# BrewMonitorEagle.net
KiCad netlist of a schematic drawn in EAGLE
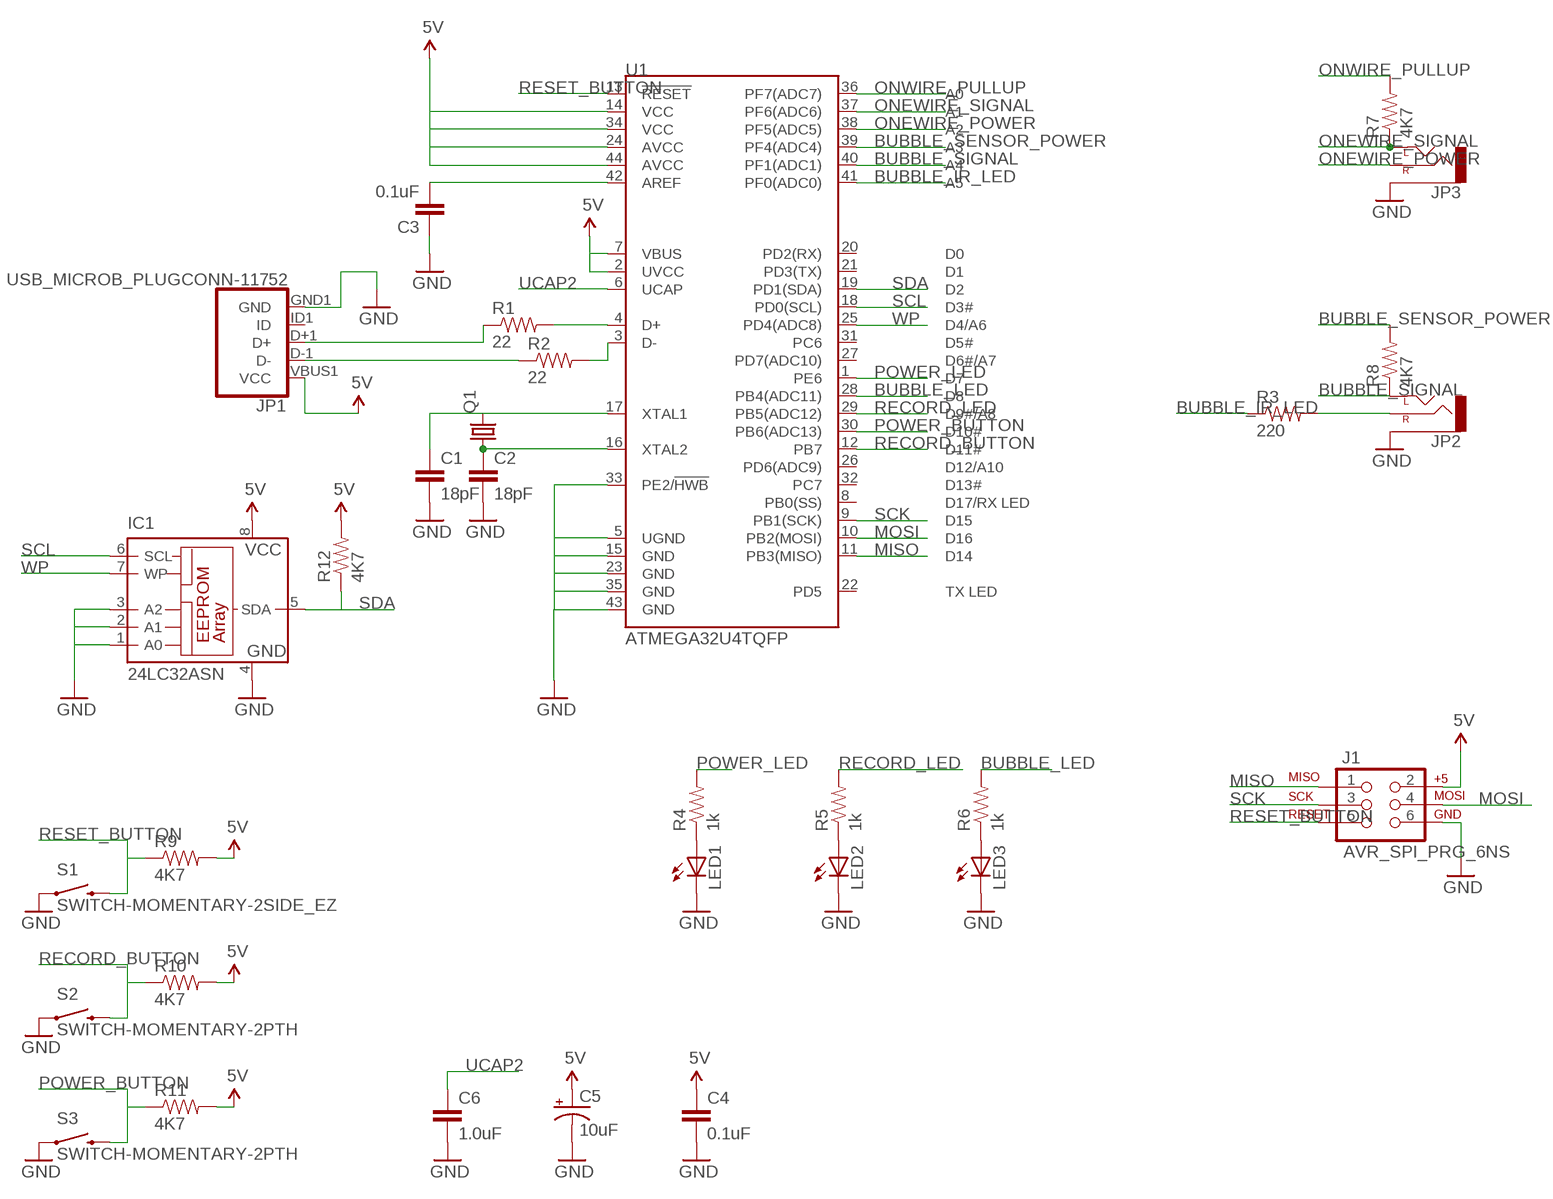
[diagram p0: schematic, sheet 1]

(export (version "E")
  (design (tool "Eeschema 10.0.6"))
  (components
    (comp (ref "C1")
      (value "18pF")
      (footprint "eagle-import:0603-CAP")
      (libsource (lib "eagle-import") (part "18PF-50V-5%(0603)"))
    )
    (comp (ref "C2")
      (value "18pF")
      (footprint "eagle-import:0603-CAP")
      (libsource (lib "eagle-import") (part "18PF-50V-5%(0603)"))
    )
    (comp (ref "C3")
      (value "0.1uF")
      (footprint "eagle-import:0603-CAP")
      (libsource (lib "eagle-import") (part "0.1UF-25V(+80/-20%)(0603)"))
    )
    (comp (ref "C4")
      (value "0.1uF")
      (footprint "eagle-import:0603-CAP")
      (libsource (lib "eagle-import") (part "0.1UF-25V(+80/-20%)(0603)"))
    )
    (comp (ref "C5")
      (value "10uF")
      (footprint "eagle-import:EIA3216")
      (libsource (lib "eagle-import") (part "10UF-16V-10%(TANT)"))
    )
    (comp (ref "C6")
      (value "1.0uF")
      (footprint "eagle-import:0603-CAP")
      (libsource (lib "eagle-import") (part "1.0UF-16V-10%(0603)"))
    )
    (comp (ref "IC1")
      (value "24LC32ASN")
      (footprint "eagle-import:SO-08")
      (fields (field (name "MF") "MICROCHIP") (field (name "MPN") "24LC32A/SN"))
      (libsource (lib "eagle-import") (part "24SNLC32A"))
    )
    (comp (ref "J1")
      (value "AVR_SPI_PRG_6NS")
      (footprint "eagle-import:2X3-NS")
      (libsource (lib "eagle-import") (part "AVR_SPI_PRG_6NS"))
    )
    (comp (ref "JP1")
      (value "USB_MICROB_PLUGCONN-11752")
      (footprint "eagle-import:USB-B-MICRO-SMD_V03")
      (libsource (lib "eagle-import") (part "USB_MICROB_PLUGCONN-11752"))
    )
    (comp (ref "JP2")
      (value "AUDIO-JACKSMD2")
      (footprint "eagle-import:AUDIO-JACK-3.5MM-SMD")
      (libsource (lib "eagle-import") (part "AUDIO-JACKSMD2"))
    )
    (comp (ref "JP3")
      (value "AUDIO-JACKSMD2")
      (footprint "eagle-import:AUDIO-JACK-3.5MM-SMD")
      (libsource (lib "eagle-import") (part "AUDIO-JACKSMD2"))
    )
    (comp (ref "LED1")
      (value "LED-3MM-NO_SILK")
      (footprint "eagle-import:LED3MM-NS")
      (libsource (lib "eagle-import") (part "LED-3MM-NO_SILK"))
    )
    (comp (ref "LED2")
      (value "LED-3MM-NO_SILK")
      (footprint "eagle-import:LED3MM-NS")
      (libsource (lib "eagle-import") (part "LED-3MM-NO_SILK"))
    )
    (comp (ref "LED3")
      (value "LED-3MM-NO_SILK")
      (footprint "eagle-import:LED3MM-NS")
      (libsource (lib "eagle-import") (part "LED-3MM-NO_SILK"))
    )
    (comp (ref "Q1")
      (value "CRYSTALHC49UP")
      (footprint "eagle-import:HC49UP")
      (libsource (lib "eagle-import") (part "CRYSTALHC49UP"))
    )
    (comp (ref "R1")
      (value "22")
      (footprint "eagle-import:0603-RES")
      (libsource (lib "eagle-import") (part "22OHM1/10W1%(0603)"))
    )
    (comp (ref "R2")
      (value "22")
      (footprint "eagle-import:0603-RES")
      (libsource (lib "eagle-import") (part "22OHM1/10W1%(0603)"))
    )
    (comp (ref "R3")
      (value "220")
      (footprint "eagle-import:0603-RES")
      (libsource (lib "eagle-import") (part "220-5%"))
    )
    (comp (ref "R4")
      (value "1k")
      (footprint "eagle-import:0603-RES")
      (libsource (lib "eagle-import") (part "1K-1%"))
    )
    (comp (ref "R5")
      (value "1k")
      (footprint "eagle-import:0603-RES")
      (libsource (lib "eagle-import") (part "1K-1%"))
    )
    (comp (ref "R6")
      (value "1k")
      (footprint "eagle-import:0603-RES")
      (libsource (lib "eagle-import") (part "1K-1%"))
    )
    (comp (ref "R7")
      (value "4K7")
      (footprint "eagle-import:0603")
      (libsource (lib "eagle-import") (part "4.7KOHM1/10W1%(0603)"))
    )
    (comp (ref "R8")
      (value "4K7")
      (footprint "eagle-import:0603")
      (libsource (lib "eagle-import") (part "4.7KOHM1/10W1%(0603)"))
    )
    (comp (ref "R9")
      (value "4K7")
      (footprint "eagle-import:0603")
      (libsource (lib "eagle-import") (part "4.7KOHM1/10W1%(0603)"))
    )
    (comp (ref "R10")
      (value "4K7")
      (footprint "eagle-import:0603")
      (libsource (lib "eagle-import") (part "4.7KOHM1/10W1%(0603)"))
    )
    (comp (ref "R11")
      (value "4K7")
      (footprint "eagle-import:0603")
      (libsource (lib "eagle-import") (part "4.7KOHM1/10W1%(0603)"))
    )
    (comp (ref "R12")
      (value "4K7")
      (footprint "eagle-import:0603")
      (libsource (lib "eagle-import") (part "4.7KOHM1/10W1%(0603)"))
    )
    (comp (ref "S1")
      (value "SWITCH-MOMENTARY-2SIDE_EZ")
      (footprint "eagle-import:TACTILE-PTH-SIDEEZ")
      (libsource (lib "eagle-import") (part "SWITCH-MOMENTARY-2SIDE_EZ"))
    )
    (comp (ref "S2")
      (value "SWITCH-MOMENTARY-2PTH")
      (footprint "eagle-import:TACTILE-PTH")
      (libsource (lib "eagle-import") (part "SWITCH-MOMENTARY-2PTH"))
    )
    (comp (ref "S3")
      (value "SWITCH-MOMENTARY-2PTH")
      (footprint "eagle-import:TACTILE-PTH")
      (libsource (lib "eagle-import") (part "SWITCH-MOMENTARY-2PTH"))
    )
    (comp (ref "U1")
      (value "ATMEGA32U4TQFP")
      (footprint "eagle-import:SPARKFUN-DIGITALIC_TQFP44")
      (libsource (lib "eagle-import") (part "ATMEGA32U4TQFP"))
    )
  )
  (nets
    (net (code "1") (name "/BUBBLE_IR_LED") (class "Default")
      (node (ref "R3") (pin "1") (pinfunction "1_1") (pintype "passive"))
      (node (ref "U1") (pin "41") (pinfunction "PF0(ADC0)_41") (pintype "bidirectional"))
    )
    (net (code "2") (name "/BUBBLE_LED") (class "Default")
      (node (ref "R6") (pin "2") (pinfunction "2_2") (pintype "passive"))
      (node (ref "U1") (pin "28") (pinfunction "PB4(ADC11)_28") (pintype "bidirectional"))
    )
    (net (code "3") (name "/BUBBLE_SENSOR_POWER") (class "Default")
      (node (ref "R8") (pin "2") (pinfunction "2_2") (pintype "passive"))
      (node (ref "U1") (pin "39") (pinfunction "PF4(ADC4)_39") (pintype "bidirectional"))
    )
    (net (code "4") (name "/BUBBLE_SIGNAL") (class "Default")
      (node (ref "JP2") (pin "TIP") (pinfunction "LEFT_TIP") (pintype "bidirectional"))
      (node (ref "R8") (pin "1") (pinfunction "1_1") (pintype "passive"))
      (node (ref "U1") (pin "40") (pinfunction "PF1(ADC1)_40") (pintype "bidirectional"))
    )
    (net (code "5") (name "/MISO") (class "Default")
      (node (ref "J1") (pin "1") (pinfunction "1_1") (pintype "passive"))
      (node (ref "U1") (pin "11") (pinfunction "PB3(MISO)_11") (pintype "bidirectional"))
    )
    (net (code "6") (name "/MOSI") (class "Default")
      (node (ref "J1") (pin "4") (pinfunction "4_4") (pintype "passive"))
      (node (ref "U1") (pin "10") (pinfunction "PB2(MOSI)_10") (pintype "bidirectional"))
    )
    (net (code "7") (name "/ONEWIRE_POWER") (class "Default")
      (node (ref "JP3") (pin "RING") (pinfunction "RIGHT_RING") (pintype "bidirectional"))
      (node (ref "U1") (pin "38") (pinfunction "PF5(ADC5)_38") (pintype "bidirectional"))
    )
    (net (code "8") (name "/ONEWIRE_SIGNAL") (class "Default")
      (node (ref "JP3") (pin "TIP") (pinfunction "LEFT_TIP") (pintype "bidirectional"))
      (node (ref "R7") (pin "1") (pinfunction "1_1") (pintype "passive"))
      (node (ref "U1") (pin "37") (pinfunction "PF6(ADC6)_37") (pintype "bidirectional"))
    )
    (net (code "9") (name "/ONWIRE_PULLUP") (class "Default")
      (node (ref "R7") (pin "2") (pinfunction "2_2") (pintype "passive"))
      (node (ref "U1") (pin "36") (pinfunction "PF7(ADC7)_36") (pintype "bidirectional"))
    )
    (net (code "10") (name "/POWER_BUTTON") (class "Default")
      (node (ref "R11") (pin "1") (pinfunction "1_1") (pintype "passive"))
      (node (ref "S3") (pin "3") (pinfunction "2_3") (pintype "passive"))
      (node (ref "U1") (pin "30") (pinfunction "PB6(ADC13)_30") (pintype "bidirectional"))
    )
    (net (code "11") (name "/POWER_LED") (class "Default")
      (node (ref "R4") (pin "2") (pinfunction "2_2") (pintype "passive"))
      (node (ref "U1") (pin "1") (pinfunction "PE6_1") (pintype "bidirectional"))
    )
    (net (code "12") (name "/RECORD_BUTTON") (class "Default")
      (node (ref "R10") (pin "1") (pinfunction "1_1") (pintype "passive"))
      (node (ref "S2") (pin "3") (pinfunction "2_3") (pintype "passive"))
      (node (ref "U1") (pin "12") (pinfunction "PB7_12") (pintype "bidirectional"))
    )
    (net (code "13") (name "/RECORD_LED") (class "Default")
      (node (ref "R5") (pin "2") (pinfunction "2_2") (pintype "passive"))
      (node (ref "U1") (pin "29") (pinfunction "PB5(ADC12)_29") (pintype "bidirectional"))
    )
    (net (code "14") (name "/RESET_BUTTON") (class "Default")
      (node (ref "J1") (pin "5") (pinfunction "5_5") (pintype "passive"))
      (node (ref "R9") (pin "1") (pinfunction "1_1") (pintype "passive"))
      (node (ref "S1") (pin "2") (pinfunction "2_2") (pintype "passive"))
      (node (ref "U1") (pin "13") (pinfunction "~{RESET}_13") (pintype "bidirectional"))
    )
    (net (code "15") (name "/SCK") (class "Default")
      (node (ref "J1") (pin "3") (pinfunction "3_3") (pintype "passive"))
      (node (ref "U1") (pin "9") (pinfunction "PB1(SCK)_9") (pintype "bidirectional"))
    )
    (net (code "16") (name "/SCL") (class "Default")
      (node (ref "IC1") (pin "6") (pinfunction "SCL_6") (pintype "input"))
      (node (ref "U1") (pin "18") (pinfunction "PD0(SCL)_18") (pintype "bidirectional"))
    )
    (net (code "17") (name "/SDA") (class "Default")
      (node (ref "IC1") (pin "5") (pinfunction "SDA_5") (pintype "bidirectional"))
      (node (ref "R12") (pin "1") (pinfunction "1_1") (pintype "passive"))
      (node (ref "U1") (pin "19") (pinfunction "PD1(SDA)_19") (pintype "bidirectional"))
    )
    (net (code "18") (name "/UCAP2") (class "Default")
      (node (ref "C6") (pin "1") (pinfunction "1_1") (pintype "passive"))
      (node (ref "U1") (pin "6") (pinfunction "UCAP_6") (pintype "bidirectional"))
    )
    (net (code "19") (name "/WP") (class "Default")
      (node (ref "IC1") (pin "7") (pinfunction "WP_7") (pintype "input"))
      (node (ref "U1") (pin "25") (pinfunction "PD4(ADC8)_25") (pintype "bidirectional"))
    )
    (net (code "20") (name "5V") (class "Default")
      (node (ref "C4") (pin "1") (pinfunction "1_1") (pintype "passive"))
      (node (ref "C5") (pin "A") (pinfunction "+_A") (pintype "passive"))
      (node (ref "IC1") (pin "8") (pinfunction "VCC_8") (pintype "power_in"))
      (node (ref "J1") (pin "2") (pinfunction "2_2") (pintype "passive"))
      (node (ref "JP1") (pin "VBUS1") (pinfunction "VCC_VBUS1") (pintype "bidirectional"))
      (node (ref "R10") (pin "2") (pinfunction "2_2") (pintype "passive"))
      (node (ref "R11") (pin "2") (pinfunction "2_2") (pintype "passive"))
      (node (ref "R12") (pin "2") (pinfunction "2_2") (pintype "passive"))
      (node (ref "R9") (pin "2") (pinfunction "2_2") (pintype "passive"))
      (node (ref "U1") (pin "14") (pinfunction "VCC_14") (pintype "bidirectional"))
      (node (ref "U1") (pin "2") (pinfunction "UVCC_2") (pintype "bidirectional"))
      (node (ref "U1") (pin "24") (pinfunction "AVCC_24") (pintype "bidirectional"))
      (node (ref "U1") (pin "34") (pinfunction "VCC_34") (pintype "bidirectional"))
      (node (ref "U1") (pin "44") (pinfunction "AVCC_44") (pintype "bidirectional"))
      (node (ref "U1") (pin "7") (pinfunction "VBUS_7") (pintype "bidirectional"))
    )
    (net (code "21") (name "GND") (class "Default")
      (node (ref "C1") (pin "2") (pinfunction "2_2") (pintype "passive"))
      (node (ref "C2") (pin "2") (pinfunction "2_2") (pintype "passive"))
      (node (ref "C3") (pin "1") (pinfunction "1_1") (pintype "passive"))
      (node (ref "C4") (pin "2") (pinfunction "2_2") (pintype "passive"))
      (node (ref "C5") (pin "C") (pinfunction "-_C") (pintype "passive"))
      (node (ref "C6") (pin "2") (pinfunction "2_2") (pintype "passive"))
      (node (ref "IC1") (pin "1") (pinfunction "A0_1") (pintype "input"))
      (node (ref "IC1") (pin "2") (pinfunction "A1_2") (pintype "input"))
      (node (ref "IC1") (pin "3") (pinfunction "A2_3") (pintype "input"))
      (node (ref "IC1") (pin "4") (pinfunction "GND_4") (pintype "power_in"))
      (node (ref "J1") (pin "6") (pinfunction "6_6") (pintype "passive"))
      (node (ref "JP1") (pin "GND1") (pinfunction "GND_GND1") (pintype "bidirectional"))
      (node (ref "JP2") (pin "SLEEVE") (pinfunction "SLEEVE_SLEEVE") (pintype "bidirectional"))
      (node (ref "JP3") (pin "SLEEVE") (pinfunction "SLEEVE_SLEEVE") (pintype "bidirectional"))
      (node (ref "LED1") (pin "K") (pinfunction "C_K") (pintype "passive"))
      (node (ref "LED2") (pin "K") (pinfunction "C_K") (pintype "passive"))
      (node (ref "LED3") (pin "K") (pinfunction "C_K") (pintype "passive"))
      (node (ref "S1") (pin "1") (pinfunction "1_1") (pintype "passive"))
      (node (ref "S2") (pin "1") (pinfunction "1_1") (pintype "passive"))
      (node (ref "S3") (pin "1") (pinfunction "1_1") (pintype "passive"))
      (node (ref "U1") (pin "15") (pinfunction "GND_15") (pintype "bidirectional"))
      (node (ref "U1") (pin "23") (pinfunction "GND_23") (pintype "bidirectional"))
      (node (ref "U1") (pin "33") (pinfunction "PE2/~{HWB}_33") (pintype "bidirectional"))
      (node (ref "U1") (pin "35") (pinfunction "GND_35") (pintype "bidirectional"))
      (node (ref "U1") (pin "43") (pinfunction "GND_43") (pintype "bidirectional"))
      (node (ref "U1") (pin "5") (pinfunction "UGND_5") (pintype "bidirectional"))
    )
    (net (code "22") (name "Net-(JP1-D+)") (class "Default")
      (node (ref "JP1") (pin "D+1") (pinfunction "D+_D+1") (pintype "bidirectional"))
      (node (ref "R1") (pin "1") (pinfunction "1_1") (pintype "passive"))
    )
    (net (code "23") (name "Net-(JP1-D-)") (class "Default")
      (node (ref "JP1") (pin "D-1") (pinfunction "D-_D-1") (pintype "bidirectional"))
      (node (ref "R2") (pin "1") (pinfunction "1_1") (pintype "passive"))
    )
    (net (code "24") (name "Net-(JP2-RIGHT)") (class "Default")
      (node (ref "JP2") (pin "RING") (pinfunction "RIGHT_RING") (pintype "bidirectional"))
      (node (ref "R3") (pin "2") (pinfunction "2_2") (pintype "passive"))
    )
    (net (code "25") (name "Net-(LED1-PadA)") (class "Default")
      (node (ref "LED1") (pin "A") (pinfunction "A_A") (pintype "passive"))
      (node (ref "R4") (pin "1") (pinfunction "1_1") (pintype "passive"))
    )
    (net (code "26") (name "Net-(LED2-PadA)") (class "Default")
      (node (ref "LED2") (pin "A") (pinfunction "A_A") (pintype "passive"))
      (node (ref "R5") (pin "1") (pinfunction "1_1") (pintype "passive"))
    )
    (net (code "27") (name "Net-(LED3-PadA)") (class "Default")
      (node (ref "LED3") (pin "A") (pinfunction "A_A") (pintype "passive"))
      (node (ref "R6") (pin "1") (pinfunction "1_1") (pintype "passive"))
    )
    (net (code "28") (name "Net-(U1-AREF)") (class "Default")
      (node (ref "C3") (pin "2") (pinfunction "2_2") (pintype "passive"))
      (node (ref "U1") (pin "42") (pinfunction "AREF_42") (pintype "bidirectional"))
    )
    (net (code "29") (name "Net-(U1-D+)") (class "Default")
      (node (ref "R1") (pin "2") (pinfunction "2_2") (pintype "passive"))
      (node (ref "U1") (pin "4") (pinfunction "D+_4") (pintype "bidirectional"))
    )
    (net (code "30") (name "Net-(U1-D-)") (class "Default")
      (node (ref "R2") (pin "2") (pinfunction "2_2") (pintype "passive"))
      (node (ref "U1") (pin "3") (pinfunction "D-_3") (pintype "bidirectional"))
    )
    (net (code "31") (name "Net-(U1-XTAL1)") (class "Default")
      (node (ref "C1") (pin "1") (pinfunction "1_1") (pintype "passive"))
      (node (ref "Q1") (pin "2") (pinfunction "2_2") (pintype "passive"))
      (node (ref "U1") (pin "17") (pinfunction "XTAL1_17") (pintype "bidirectional"))
    )
    (net (code "32") (name "Net-(U1-XTAL2)") (class "Default")
      (node (ref "C2") (pin "1") (pinfunction "1_1") (pintype "passive"))
      (node (ref "Q1") (pin "1") (pinfunction "1_1") (pintype "passive"))
      (node (ref "U1") (pin "16") (pinfunction "XTAL2_16") (pintype "bidirectional"))
    )
    (net (code "33") (name "unconnected-(JP1-ID-PadID1)") (class "Default")
      (node (ref "JP1") (pin "ID1") (pinfunction "ID_ID1") (pintype "bidirectional"))
    )
    (net (code "34") (name "unconnected-(U1-PB0(SS)-Pad8)") (class "Default")
      (node (ref "U1") (pin "8") (pinfunction "PB0(SS)_8") (pintype "bidirectional"))
    )
    (net (code "35") (name "unconnected-(U1-PC6-Pad31)") (class "Default")
      (node (ref "U1") (pin "31") (pinfunction "PC6_31") (pintype "bidirectional"))
    )
    (net (code "36") (name "unconnected-(U1-PC7-Pad32)") (class "Default")
      (node (ref "U1") (pin "32") (pinfunction "PC7_32") (pintype "bidirectional"))
    )
    (net (code "37") (name "unconnected-(U1-PD2(RX)-Pad20)") (class "Default")
      (node (ref "U1") (pin "20") (pinfunction "PD2(RX)_20") (pintype "bidirectional"))
    )
    (net (code "38") (name "unconnected-(U1-PD3(TX)-Pad21)") (class "Default")
      (node (ref "U1") (pin "21") (pinfunction "PD3(TX)_21") (pintype "bidirectional"))
    )
    (net (code "39") (name "unconnected-(U1-PD5-Pad22)") (class "Default")
      (node (ref "U1") (pin "22") (pinfunction "PD5_22") (pintype "bidirectional"))
    )
    (net (code "40") (name "unconnected-(U1-PD6(ADC9)-Pad26)") (class "Default")
      (node (ref "U1") (pin "26") (pinfunction "PD6(ADC9)_26") (pintype "bidirectional"))
    )
    (net (code "41") (name "unconnected-(U1-PD7(ADC10)-Pad27)") (class "Default")
      (node (ref "U1") (pin "27") (pinfunction "PD7(ADC10)_27") (pintype "bidirectional"))
    )
  )
)
